# balloon-v03.net
KiCad netlist of a schematic drawn in EAGLE
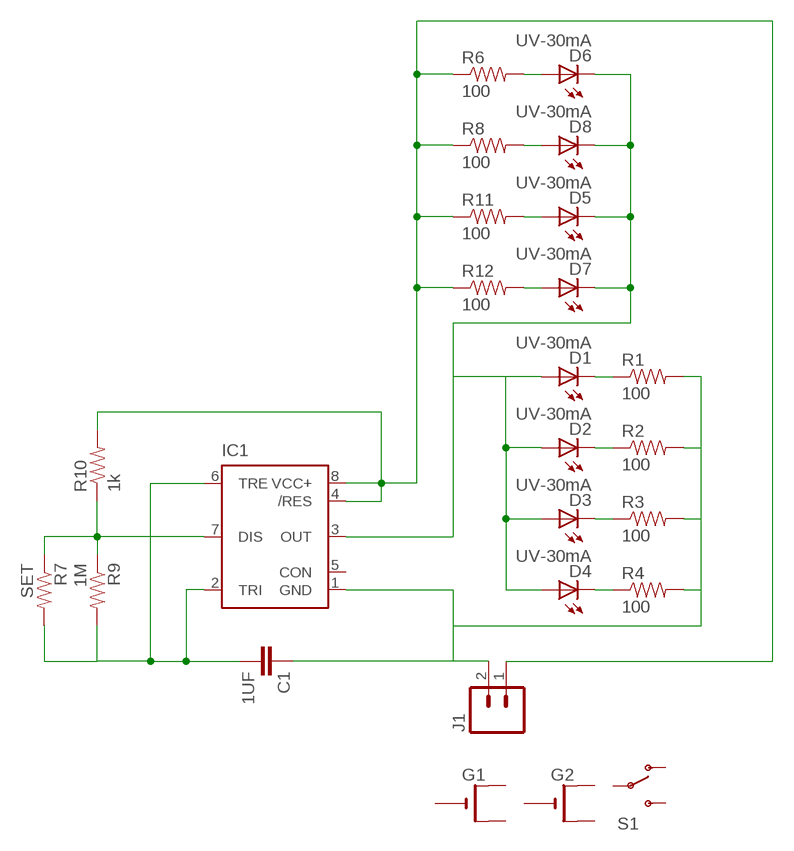
[diagram p0: schematic, sheet 1]

(export (version "E")
  (design (tool "Eeschema 10.0.6"))
  (components
    (comp (ref "C1")
      (value "1UF")
      (footprint "eagle-import:0603-CAP")
      (libsource (lib "eagle-import") (part "CAP0603-CAP"))
    )
    (comp (ref "D1")
      (value "UV-30mA")
      (footprint "eagle-import:CHIPLED_0603")
      (libsource (lib "eagle-import") (part "LEDCHIPLED_0603"))
    )
    (comp (ref "D2")
      (value "UV-30mA")
      (footprint "eagle-import:CHIPLED_0603")
      (libsource (lib "eagle-import") (part "LEDCHIPLED_0603"))
    )
    (comp (ref "D3")
      (value "UV-30mA")
      (footprint "eagle-import:CHIPLED_0603")
      (libsource (lib "eagle-import") (part "LEDCHIPLED_0603"))
    )
    (comp (ref "D4")
      (value "UV-30mA")
      (footprint "eagle-import:CHIPLED_0603")
      (libsource (lib "eagle-import") (part "LEDCHIPLED_0603"))
    )
    (comp (ref "D5")
      (value "UV-30mA")
      (footprint "eagle-import:CHIPLED_0603")
      (libsource (lib "eagle-import") (part "LEDCHIPLED_0603"))
    )
    (comp (ref "D6")
      (value "UV-30mA")
      (footprint "eagle-import:CHIPLED_0603")
      (libsource (lib "eagle-import") (part "LEDCHIPLED_0603"))
    )
    (comp (ref "D7")
      (value "UV-30mA")
      (footprint "eagle-import:CHIPLED_0603")
      (libsource (lib "eagle-import") (part "LEDCHIPLED_0603"))
    )
    (comp (ref "D8")
      (value "UV-30mA")
      (footprint "eagle-import:CHIPLED_0603")
      (libsource (lib "eagle-import") (part "LEDCHIPLED_0603"))
    )
    (comp (ref "G1")
      (value "CR2032SMT")
      (footprint "eagle-import:CR2032-SMD")
      (libsource (lib "eagle-import") (part "CR2032SMT"))
    )
    (comp (ref "G2")
      (value "CR2032SMT")
      (footprint "eagle-import:CR2032-SMD")
      (libsource (lib "eagle-import") (part "CR2032SMT"))
    )
    (comp (ref "IC1")
      (value "NE555D")
      (footprint "eagle-import:SO08")
      (libsource (lib "eagle-import") (part "NE555D"))
    )
    (comp (ref "J1")
      (value "M02PTH3")
      (footprint "eagle-import:1X02_LONGPADS")
      (libsource (lib "eagle-import") (part "M02PTH3"))
    )
    (comp (ref "R1")
      (value "100")
      (footprint "eagle-import:0603-RES")
      (libsource (lib "eagle-import") (part "RESISTOR0603-RES"))
    )
    (comp (ref "R2")
      (value "100")
      (footprint "eagle-import:0603-RES")
      (libsource (lib "eagle-import") (part "RESISTOR0603-RES"))
    )
    (comp (ref "R3")
      (value "100")
      (footprint "eagle-import:0603-RES")
      (libsource (lib "eagle-import") (part "RESISTOR0603-RES"))
    )
    (comp (ref "R4")
      (value "100")
      (footprint "eagle-import:0603-RES")
      (libsource (lib "eagle-import") (part "RESISTOR0603-RES"))
    )
    (comp (ref "R6")
      (value "100")
      (footprint "eagle-import:0603-RES")
      (libsource (lib "eagle-import") (part "RESISTOR0603-RES"))
    )
    (comp (ref "R7")
      (value "SET")
      (footprint "eagle-import:0603-RES")
      (libsource (lib "eagle-import") (part "RESISTOR0603"))
    )
    (comp (ref "R8")
      (value "100")
      (footprint "eagle-import:0603-RES")
      (libsource (lib "eagle-import") (part "RESISTOR0603-RES"))
    )
    (comp (ref "R9")
      (value "1M")
      (footprint "eagle-import:0603-RES")
      (libsource (lib "eagle-import") (part "RESISTOR0603-RES"))
    )
    (comp (ref "R10")
      (value "1k")
      (footprint "eagle-import:0603-RES")
      (libsource (lib "eagle-import") (part "RESISTOR0603-RES"))
    )
    (comp (ref "R11")
      (value "100")
      (footprint "eagle-import:0603-RES")
      (libsource (lib "eagle-import") (part "RESISTOR0603-RES"))
    )
    (comp (ref "R12")
      (value "100")
      (footprint "eagle-import:0603-RES")
      (libsource (lib "eagle-import") (part "RESISTOR0603-RES"))
    )
    (comp (ref "S1")
      (value "SWITCH-SPDT-SMD-A")
      (footprint "eagle-import:SWITCH-SPST-SMD-A")
      (libsource (lib "eagle-import") (part "SWITCH-SPDT-SMD-A"))
    )
  )
  (nets
    (net (code "1") (name "Net-(D1-PadC)") (class "Default")
      (node (ref "D1") (pin "C") (pinfunction "C_C") (pintype "passive"))
      (node (ref "R1") (pin "1") (pinfunction "1_1") (pintype "passive"))
    )
    (net (code "2") (name "Net-(D2-PadC)") (class "Default")
      (node (ref "D2") (pin "C") (pinfunction "C_C") (pintype "passive"))
      (node (ref "R2") (pin "1") (pinfunction "1_1") (pintype "passive"))
    )
    (net (code "3") (name "Net-(D3-PadC)") (class "Default")
      (node (ref "D3") (pin "C") (pinfunction "C_C") (pintype "passive"))
      (node (ref "R3") (pin "1") (pinfunction "1_1") (pintype "passive"))
    )
    (net (code "4") (name "Net-(D4-PadC)") (class "Default")
      (node (ref "D4") (pin "C") (pinfunction "C_C") (pintype "passive"))
      (node (ref "R4") (pin "1") (pinfunction "1_1") (pintype "passive"))
    )
    (net (code "5") (name "Net-(D5-PadA)") (class "Default")
      (node (ref "D5") (pin "A") (pinfunction "A_A") (pintype "passive"))
      (node (ref "R11") (pin "2") (pinfunction "2_2") (pintype "passive"))
    )
    (net (code "6") (name "Net-(D6-PadA)") (class "Default")
      (node (ref "D6") (pin "A") (pinfunction "A_A") (pintype "passive"))
      (node (ref "R6") (pin "2") (pinfunction "2_2") (pintype "passive"))
    )
    (net (code "7") (name "Net-(D7-PadA)") (class "Default")
      (node (ref "D7") (pin "A") (pinfunction "A_A") (pintype "passive"))
      (node (ref "R12") (pin "2") (pinfunction "2_2") (pintype "passive"))
    )
    (net (code "8") (name "Net-(D8-PadA)") (class "Default")
      (node (ref "D8") (pin "A") (pinfunction "A_A") (pintype "passive"))
      (node (ref "R8") (pin "2") (pinfunction "2_2") (pintype "passive"))
    )
    (net (code "9") (name "Net-(IC1-DIS)") (class "Default")
      (node (ref "IC1") (pin "7") (pinfunction "DIS_7") (pintype "input"))
      (node (ref "R10") (pin "1") (pinfunction "1_1") (pintype "passive"))
      (node (ref "R7") (pin "1") (pinfunction "1_1") (pintype "passive"))
      (node (ref "R9") (pin "1") (pinfunction "1_1") (pintype "passive"))
    )
    (net (code "10") (name "Net-(IC1-GND)") (class "Default")
      (node (ref "C1") (pin "1") (pinfunction "1_1") (pintype "passive"))
      (node (ref "IC1") (pin "1") (pinfunction "GND_1") (pintype "power_in"))
      (node (ref "J1") (pin "2") (pinfunction "2_2") (pintype "passive"))
      (node (ref "R1") (pin "2") (pinfunction "2_2") (pintype "passive"))
      (node (ref "R2") (pin "2") (pinfunction "2_2") (pintype "passive"))
      (node (ref "R3") (pin "2") (pinfunction "2_2") (pintype "passive"))
      (node (ref "R4") (pin "2") (pinfunction "2_2") (pintype "passive"))
    )
    (net (code "11") (name "Net-(IC1-OUT)") (class "Default")
      (node (ref "D1") (pin "A") (pinfunction "A_A") (pintype "passive"))
      (node (ref "D2") (pin "A") (pinfunction "A_A") (pintype "passive"))
      (node (ref "D3") (pin "A") (pinfunction "A_A") (pintype "passive"))
      (node (ref "D4") (pin "A") (pinfunction "A_A") (pintype "passive"))
      (node (ref "D5") (pin "C") (pinfunction "C_C") (pintype "passive"))
      (node (ref "D6") (pin "C") (pinfunction "C_C") (pintype "passive"))
      (node (ref "D7") (pin "C") (pinfunction "C_C") (pintype "passive"))
      (node (ref "D8") (pin "C") (pinfunction "C_C") (pintype "passive"))
      (node (ref "IC1") (pin "3") (pinfunction "OUT_3") (pintype "output"))
    )
    (net (code "12") (name "Net-(IC1-TRE)") (class "Default")
      (node (ref "C1") (pin "2") (pinfunction "2_2") (pintype "passive"))
      (node (ref "IC1") (pin "2") (pinfunction "TRI_2") (pintype "input"))
      (node (ref "IC1") (pin "6") (pinfunction "TRE_6") (pintype "input"))
      (node (ref "R7") (pin "2") (pinfunction "2_2") (pintype "passive"))
      (node (ref "R9") (pin "2") (pinfunction "2_2") (pintype "passive"))
    )
    (net (code "13") (name "Net-(IC1-VCC+)") (class "Default")
      (node (ref "IC1") (pin "4") (pinfunction "/RES_4") (pintype "input"))
      (node (ref "IC1") (pin "8") (pinfunction "VCC+_8") (pintype "power_in"))
      (node (ref "J1") (pin "1") (pinfunction "1_1") (pintype "passive"))
      (node (ref "R10") (pin "2") (pinfunction "2_2") (pintype "passive"))
      (node (ref "R11") (pin "1") (pinfunction "1_1") (pintype "passive"))
      (node (ref "R12") (pin "1") (pinfunction "1_1") (pintype "passive"))
      (node (ref "R6") (pin "1") (pinfunction "1_1") (pintype "passive"))
      (node (ref "R8") (pin "1") (pinfunction "1_1") (pintype "passive"))
    )
    (net (code "14") (name "unconnected-(G1-+-Pad+$1)") (class "Default")
      (node (ref "G1") (pin "+$1") (pinfunction "+_+$1") (pintype "passive"))
    )
    (net (code "15") (name "unconnected-(G1-+1-Pad+$2)") (class "Default")
      (node (ref "G1") (pin "+$2") (pinfunction "+1_+$2") (pintype "passive"))
    )
    (net (code "16") (name "unconnected-(G1-Pad-)") (class "Default")
      (node (ref "G1") (pin "-") (pinfunction "-_-") (pintype "passive"))
    )
    (net (code "17") (name "unconnected-(G2-+-Pad+$1)") (class "Default")
      (node (ref "G2") (pin "+$1") (pinfunction "+_+$1") (pintype "passive"))
    )
    (net (code "18") (name "unconnected-(G2-+1-Pad+$2)") (class "Default")
      (node (ref "G2") (pin "+$2") (pinfunction "+1_+$2") (pintype "passive"))
    )
    (net (code "19") (name "unconnected-(G2-Pad-)") (class "Default")
      (node (ref "G2") (pin "-") (pinfunction "-_-") (pintype "passive"))
    )
    (net (code "20") (name "unconnected-(IC1-CON-Pad5)") (class "Default")
      (node (ref "IC1") (pin "5") (pinfunction "CON_5") (pintype "input"))
    )
    (net (code "21") (name "unconnected-(S1-O-Pad1)") (class "Default")
      (node (ref "S1") (pin "1") (pinfunction "O_1") (pintype "passive"))
    )
    (net (code "22") (name "unconnected-(S1-P-Pad2)") (class "Default")
      (node (ref "S1") (pin "2") (pinfunction "P_2") (pintype "passive"))
    )
    (net (code "23") (name "unconnected-(S1-S-Pad3)") (class "Default")
      (node (ref "S1") (pin "3") (pinfunction "S_3") (pintype "passive"))
    )
  )
)
